# Shutdown_Circuit.net
KiCad netlist of a schematic drawn in EAGLE
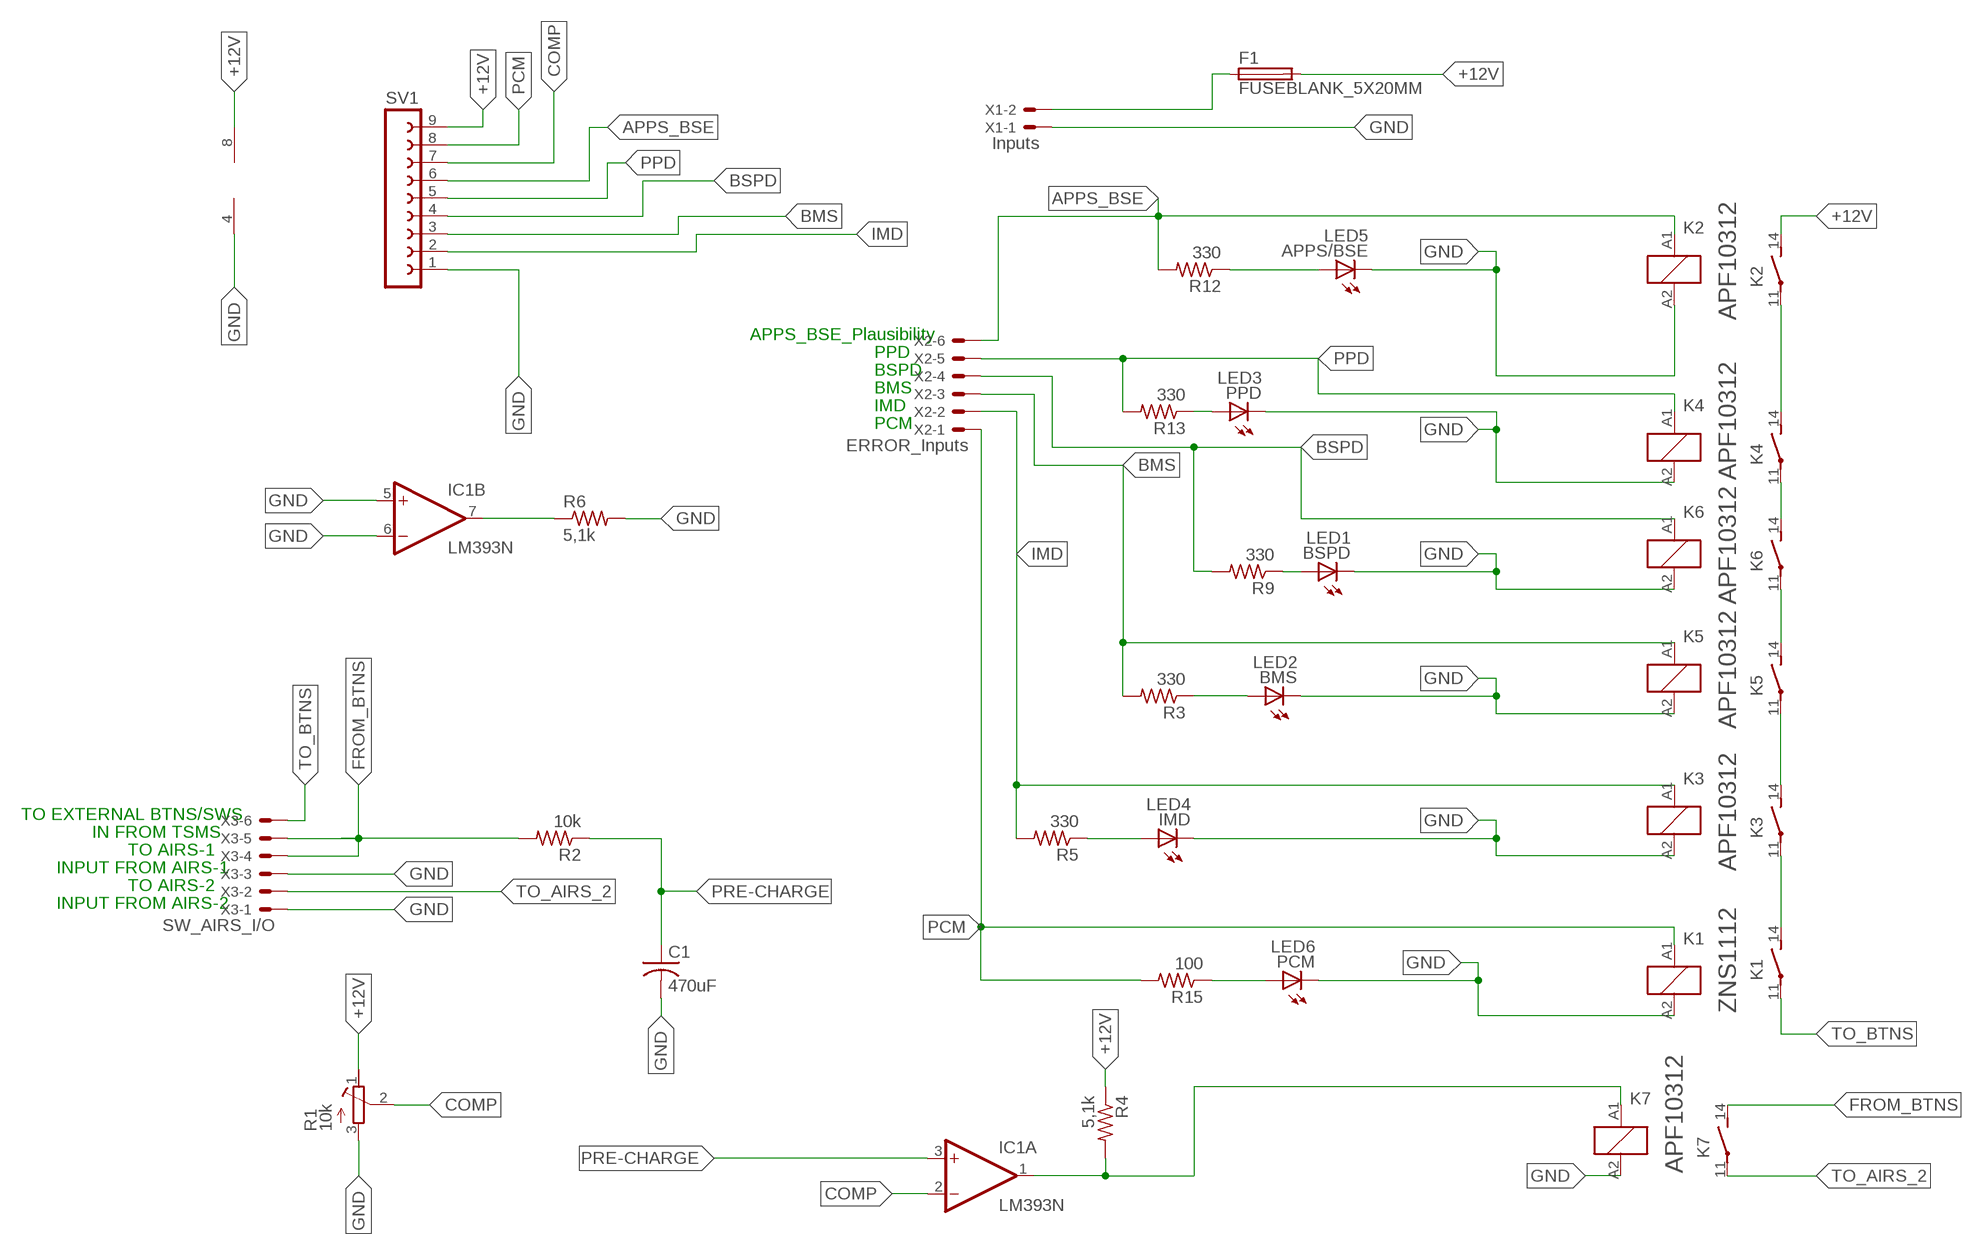
[diagram p0: schematic, sheet 1]

(export (version "E")
  (design (tool "Eeschema 10.0.6"))
  (components
    (comp (ref "APPS/BSE")
      (value "LED5")
      (footprint "eagle-import:LED3MM")
      (fields (field (name "MF") "VISHAY/TELEFUNKEN") (field (name "MPN") "TLCR5800"))
      (libsource (lib "eagle-import") (part "LED3MM"))
    )
    (comp (ref "BMS")
      (value "LED2")
      (footprint "eagle-import:LED3MM")
      (fields (field (name "MF") "VISHAY/TELEFUNKEN") (field (name "MPN") "TLCR5800"))
      (libsource (lib "eagle-import") (part "LED3MM"))
    )
    (comp (ref "BSPD")
      (value "LED1")
      (footprint "eagle-import:LED3MM")
      (fields (field (name "MF") "VISHAY/TELEFUNKEN") (field (name "MPN") "TLCR5800"))
      (libsource (lib "eagle-import") (part "LED3MM"))
    )
    (comp (ref "C1")
      (value "470uF")
      (footprint "eagle-import:C050-045X075")
      (fields (field (name "MPN") "MAL213631471E3"))
      (libsource (lib "eagle-import") (part "C-US050-045X075"))
    )
    (comp (ref "F1")
      (value "FUSEBLANK_5X20MM")
      (footprint "eagle-import:FUSE_HOLDER_5X20MM")
      (libsource (lib "eagle-import") (part "FUSEBLANK_5X20MM"))
    )
    (comp (ref "IC1")
      (value "LM393N")
      (footprint "eagle-import:DIL08")
      (fields
        (field (name "MF") "TEXAS INSTRUMENTS")
        (field (name "MPN") "LM393P")
        (field (name "OC_NEWARK") "06F9461")
      )
      (libsource (lib "eagle-import") (part "LM393N"))
    )
    (comp (ref "IMD")
      (value "LED4")
      (footprint "eagle-import:LED3MM")
      (fields (field (name "MF") "VISHAY/TELEFUNKEN") (field (name "MPN") "TLCR5800"))
      (libsource (lib "eagle-import") (part "LED3MM"))
    )
    (comp (ref "K1")
      (value "ZNS1112")
      (footprint "eagle-import:ZN1")
      (libsource (lib "eagle-import") (part "ZNS1112"))
    )
    (comp (ref "K2")
      (value "APF10312")
      (footprint "eagle-import:SNR-V1")
      (libsource (lib "eagle-import") (part "SNR1"))
    )
    (comp (ref "K3")
      (value "APF10312")
      (footprint "eagle-import:SNR-V1")
      (libsource (lib "eagle-import") (part "SNR1"))
    )
    (comp (ref "K4")
      (value "APF10312")
      (footprint "eagle-import:SNR-V1")
      (libsource (lib "eagle-import") (part "SNR1"))
    )
    (comp (ref "K5")
      (value "APF10312")
      (footprint "eagle-import:SNR-V1")
      (libsource (lib "eagle-import") (part "SNR1"))
    )
    (comp (ref "K6")
      (value "APF10312")
      (footprint "eagle-import:SNR-V1")
      (libsource (lib "eagle-import") (part "SNR1"))
    )
    (comp (ref "K7")
      (value "APF10312")
      (footprint "eagle-import:SNR-V1")
      (libsource (lib "eagle-import") (part "SNR1"))
    )
    (comp (ref "PCM")
      (value "LED6")
      (footprint "eagle-import:LED3MM")
      (fields (field (name "MF") "VISHAY/TELEFUNKEN") (field (name "MPN") "TLCR5800"))
      (libsource (lib "eagle-import") (part "LED3MM"))
    )
    (comp (ref "PPD")
      (value "LED3")
      (footprint "eagle-import:LED3MM")
      (fields (field (name "MF") "VISHAY/TELEFUNKEN") (field (name "MPN") "TLCR5800"))
      (libsource (lib "eagle-import") (part "LED3MM"))
    )
    (comp (ref "R1")
      (value "10k")
      (footprint "eagle-import:RTRIM43P")
      (fields (field (name "MF") "FARNELL") (field (name "MPN") "MF50 10K"))
      (libsource (lib "eagle-import") (part "R-TRIMM43P"))
    )
    (comp (ref "R2")
      (value "10k")
      (footprint "eagle-import:0207_10")
      (fields (field (name "MF") "FARNELL") (field (name "MPN") "MCF 0.25W 10K"))
      (libsource (lib "eagle-import") (part "R-US_0207/10"))
    )
    (comp (ref "R3")
      (value "330")
      (footprint "eagle-import:0207_10")
      (libsource (lib "eagle-import") (part "R-US_0207/10"))
    )
    (comp (ref "R4")
      (value "5,1k")
      (footprint "eagle-import:0207_10")
      (libsource (lib "eagle-import") (part "R-US_0207/10"))
    )
    (comp (ref "R5")
      (value "330")
      (footprint "eagle-import:0207_10")
      (libsource (lib "eagle-import") (part "R-US_0207/10"))
    )
    (comp (ref "R6")
      (value "5,1k")
      (footprint "eagle-import:0207_10")
      (libsource (lib "eagle-import") (part "R-US_0207/10"))
    )
    (comp (ref "R9")
      (value "330")
      (footprint "eagle-import:0207_10")
      (libsource (lib "eagle-import") (part "R-US_0207/10"))
    )
    (comp (ref "R12")
      (value "330")
      (footprint "eagle-import:0207_10")
      (libsource (lib "eagle-import") (part "R-US_0207/10"))
    )
    (comp (ref "R13")
      (value "330")
      (footprint "eagle-import:0207_10")
      (libsource (lib "eagle-import") (part "R-US_0207/10"))
    )
    (comp (ref "R15")
      (value "100")
      (footprint "eagle-import:0207_10")
      (libsource (lib "eagle-import") (part "R-US_0207/10"))
    )
    (comp (ref "SV1")
      (value "FE09W")
      (footprint "eagle-import:FE09W")
      (libsource (lib "eagle-import") (part "FE09W"))
    )
    (comp (ref "X1")
      (value "Inputs")
      (footprint "eagle-import:22-23-2021")
      (fields (field (name "MF") "MOLEX") (field (name "MPN") "22-23-2021"))
      (libsource (lib "eagle-import") (part "22-23-2021"))
    )
    (comp (ref "X2")
      (value "ERROR_Inputs")
      (footprint "eagle-import:22-23-2061")
      (fields (field (name "MF") "MOLEX") (field (name "MPN") "22-23-2061"))
      (libsource (lib "eagle-import") (part "22-23-2061"))
    )
    (comp (ref "X3")
      (value "SW_AIRS_I/O")
      (footprint "eagle-import:22-23-2061")
      (fields (field (name "MF") "MOLEX") (field (name "MPN") "22-23-2061"))
      (libsource (lib "eagle-import") (part "22-23-2061"))
    )
  )
  (nets
    (net (code "1") (name "+12V") (class "Default")
      (node (ref "F1") (pin "2") (pinfunction "2_2") (pintype "passive"))
      (node (ref "IC1") (pin "8") (pinfunction "V+_8") (pintype "power_in"))
      (node (ref "K2") (pin "14") (pinfunction "S_14") (pintype "passive"))
      (node (ref "R1") (pin "1") (pinfunction "E_1") (pintype "passive"))
      (node (ref "R4") (pin "1") (pinfunction "1_1") (pintype "passive"))
      (node (ref "SV1") (pin "9") (pinfunction "9_9") (pintype "passive"))
    )
    (net (code "2") (name "APPS_BSE") (class "Default")
      (node (ref "K2") (pin "A1") (pinfunction "1_A1") (pintype "passive"))
      (node (ref "R12") (pin "2") (pinfunction "2_2") (pintype "passive"))
      (node (ref "SV1") (pin "6") (pinfunction "6_6") (pintype "passive"))
      (node (ref "X2") (pin "6") (pinfunction "S_6") (pintype "passive"))
    )
    (net (code "3") (name "BMS") (class "Default")
      (node (ref "K5") (pin "A1") (pinfunction "1_A1") (pintype "passive"))
      (node (ref "R3") (pin "2") (pinfunction "2_2") (pintype "passive"))
      (node (ref "SV1") (pin "3") (pinfunction "3_3") (pintype "passive"))
      (node (ref "X2") (pin "3") (pinfunction "S_3") (pintype "passive"))
    )
    (net (code "4") (name "BSPD") (class "Default")
      (node (ref "K6") (pin "A1") (pinfunction "1_A1") (pintype "passive"))
      (node (ref "R9") (pin "2") (pinfunction "2_2") (pintype "passive"))
      (node (ref "SV1") (pin "4") (pinfunction "4_4") (pintype "passive"))
      (node (ref "X2") (pin "4") (pinfunction "S_4") (pintype "passive"))
    )
    (net (code "5") (name "COMP") (class "Default")
      (node (ref "IC1") (pin "2") (pinfunction "-IN_2") (pintype "input"))
      (node (ref "R1") (pin "2") (pinfunction "S_2") (pintype "passive"))
      (node (ref "SV1") (pin "7") (pinfunction "7_7") (pintype "passive"))
    )
    (net (code "6") (name "FROM_BTNS") (class "Default")
      (node (ref "K7") (pin "14") (pinfunction "S_14") (pintype "passive"))
      (node (ref "R2") (pin "2") (pinfunction "2_2") (pintype "passive"))
      (node (ref "X3") (pin "4") (pinfunction "S_4") (pintype "passive"))
      (node (ref "X3") (pin "5") (pinfunction "S_5") (pintype "passive"))
    )
    (net (code "7") (name "GND") (class "Default")
      (node (ref "APPS/BSE") (pin "K") (pinfunction "C_K") (pintype "passive"))
      (node (ref "BMS") (pin "K") (pinfunction "C_K") (pintype "passive"))
      (node (ref "BSPD") (pin "K") (pinfunction "C_K") (pintype "passive"))
      (node (ref "C1") (pin "2") (pinfunction "2_2") (pintype "passive"))
      (node (ref "IC1") (pin "4") (pinfunction "V-_4") (pintype "power_in"))
      (node (ref "IC1") (pin "5") (pinfunction "+IN_5") (pintype "input"))
      (node (ref "IC1") (pin "6") (pinfunction "-IN_6") (pintype "input"))
      (node (ref "IMD") (pin "K") (pinfunction "C_K") (pintype "passive"))
      (node (ref "K1") (pin "A2") (pinfunction "2_A2") (pintype "passive"))
      (node (ref "K2") (pin "A2") (pinfunction "2_A2") (pintype "passive"))
      (node (ref "K3") (pin "A2") (pinfunction "2_A2") (pintype "passive"))
      (node (ref "K4") (pin "A2") (pinfunction "2_A2") (pintype "passive"))
      (node (ref "K5") (pin "A2") (pinfunction "2_A2") (pintype "passive"))
      (node (ref "K6") (pin "A2") (pinfunction "2_A2") (pintype "passive"))
      (node (ref "K7") (pin "A2") (pinfunction "2_A2") (pintype "passive"))
      (node (ref "PCM") (pin "K") (pinfunction "C_K") (pintype "passive"))
      (node (ref "PPD") (pin "K") (pinfunction "C_K") (pintype "passive"))
      (node (ref "R1") (pin "3") (pinfunction "A_3") (pintype "passive"))
      (node (ref "R6") (pin "2") (pinfunction "2_2") (pintype "passive"))
      (node (ref "SV1") (pin "1") (pinfunction "1_1") (pintype "passive"))
      (node (ref "X1") (pin "1") (pinfunction "S_1") (pintype "passive"))
      (node (ref "X3") (pin "1") (pinfunction "S_1") (pintype "passive"))
      (node (ref "X3") (pin "3") (pinfunction "S_3") (pintype "passive"))
    )
    (net (code "8") (name "IMD") (class "Default")
      (node (ref "K3") (pin "A1") (pinfunction "1_A1") (pintype "passive"))
      (node (ref "R5") (pin "2") (pinfunction "2_2") (pintype "passive"))
      (node (ref "SV1") (pin "2") (pinfunction "2_2") (pintype "passive"))
      (node (ref "X2") (pin "2") (pinfunction "S_2") (pintype "passive"))
    )
    (net (code "9") (name "Net-(APPS/BSE-PadA)") (class "Default")
      (node (ref "APPS/BSE") (pin "A") (pinfunction "A_A") (pintype "passive"))
      (node (ref "R12") (pin "1") (pinfunction "1_1") (pintype "passive"))
    )
    (net (code "10") (name "Net-(BMS-PadA)") (class "Default")
      (node (ref "BMS") (pin "A") (pinfunction "A_A") (pintype "passive"))
      (node (ref "R3") (pin "1") (pinfunction "1_1") (pintype "passive"))
    )
    (net (code "11") (name "Net-(BSPD-PadA)") (class "Default")
      (node (ref "BSPD") (pin "A") (pinfunction "A_A") (pintype "passive"))
      (node (ref "R9") (pin "1") (pinfunction "1_1") (pintype "passive"))
    )
    (net (code "12") (name "Net-(IC1A-OUT)") (class "Default")
      (node (ref "IC1") (pin "1") (pinfunction "OUT_1") (pintype "output"))
      (node (ref "K7") (pin "A1") (pinfunction "1_A1") (pintype "passive"))
      (node (ref "R4") (pin "2") (pinfunction "2_2") (pintype "passive"))
    )
    (net (code "13") (name "Net-(IC1B-OUT)") (class "Default")
      (node (ref "IC1") (pin "7") (pinfunction "OUT_7") (pintype "output"))
      (node (ref "R6") (pin "1") (pinfunction "1_1") (pintype "passive"))
    )
    (net (code "14") (name "Net-(IMD-PadA)") (class "Default")
      (node (ref "IMD") (pin "A") (pinfunction "A_A") (pintype "passive"))
      (node (ref "R5") (pin "1") (pinfunction "1_1") (pintype "passive"))
    )
    (net (code "15") (name "Net-(K1B-S)") (class "Default")
      (node (ref "K1") (pin "14") (pinfunction "S_14") (pintype "passive"))
      (node (ref "K3") (pin "11") (pinfunction "P_11") (pintype "passive"))
    )
    (net (code "16") (name "Net-(K2B-P)") (class "Default")
      (node (ref "K2") (pin "11") (pinfunction "P_11") (pintype "passive"))
      (node (ref "K4") (pin "14") (pinfunction "S_14") (pintype "passive"))
    )
    (net (code "17") (name "Net-(K3B-S)") (class "Default")
      (node (ref "K3") (pin "14") (pinfunction "S_14") (pintype "passive"))
      (node (ref "K5") (pin "11") (pinfunction "P_11") (pintype "passive"))
    )
    (net (code "18") (name "Net-(K4B-P)") (class "Default")
      (node (ref "K4") (pin "11") (pinfunction "P_11") (pintype "passive"))
      (node (ref "K6") (pin "14") (pinfunction "S_14") (pintype "passive"))
    )
    (net (code "19") (name "Net-(K5B-S)") (class "Default")
      (node (ref "K5") (pin "14") (pinfunction "S_14") (pintype "passive"))
      (node (ref "K6") (pin "11") (pinfunction "P_11") (pintype "passive"))
    )
    (net (code "20") (name "Net-(PCM-PadA)") (class "Default")
      (node (ref "PCM") (pin "A") (pinfunction "A_A") (pintype "passive"))
      (node (ref "R15") (pin "1") (pinfunction "1_1") (pintype "passive"))
    )
    (net (code "21") (name "Net-(PPD-PadA)") (class "Default")
      (node (ref "PPD") (pin "A") (pinfunction "A_A") (pintype "passive"))
      (node (ref "R13") (pin "1") (pinfunction "1_1") (pintype "passive"))
    )
    (net (code "22") (name "Net-(X1B-S)") (class "Default")
      (node (ref "F1") (pin "1") (pinfunction "1_1") (pintype "passive"))
      (node (ref "X1") (pin "2") (pinfunction "S_2") (pintype "passive"))
    )
    (net (code "23") (name "PCM") (class "Default")
      (node (ref "K1") (pin "A1") (pinfunction "1_A1") (pintype "passive"))
      (node (ref "R15") (pin "2") (pinfunction "2_2") (pintype "passive"))
      (node (ref "SV1") (pin "8") (pinfunction "8_8") (pintype "passive"))
      (node (ref "X2") (pin "1") (pinfunction "S_1") (pintype "passive"))
    )
    (net (code "24") (name "PPD") (class "Default")
      (node (ref "K4") (pin "A1") (pinfunction "1_A1") (pintype "passive"))
      (node (ref "R13") (pin "2") (pinfunction "2_2") (pintype "passive"))
      (node (ref "SV1") (pin "5") (pinfunction "5_5") (pintype "passive"))
      (node (ref "X2") (pin "5") (pinfunction "S_5") (pintype "passive"))
    )
    (net (code "25") (name "PRE-CHARGE") (class "Default")
      (node (ref "C1") (pin "1") (pinfunction "1_1") (pintype "passive"))
      (node (ref "IC1") (pin "3") (pinfunction "+IN_3") (pintype "input"))
      (node (ref "R2") (pin "1") (pinfunction "1_1") (pintype "passive"))
    )
    (net (code "26") (name "TO_AIRS_2") (class "Default")
      (node (ref "K7") (pin "11") (pinfunction "P_11") (pintype "passive"))
      (node (ref "X3") (pin "2") (pinfunction "S_2") (pintype "passive"))
    )
    (net (code "27") (name "TO_BTNS") (class "Default")
      (node (ref "K1") (pin "11") (pinfunction "P_11") (pintype "passive"))
      (node (ref "X3") (pin "6") (pinfunction "S_6") (pintype "passive"))
    )
  )
)
